# Clock.net
KiCad netlist of a schematic drawn in Altium Designer
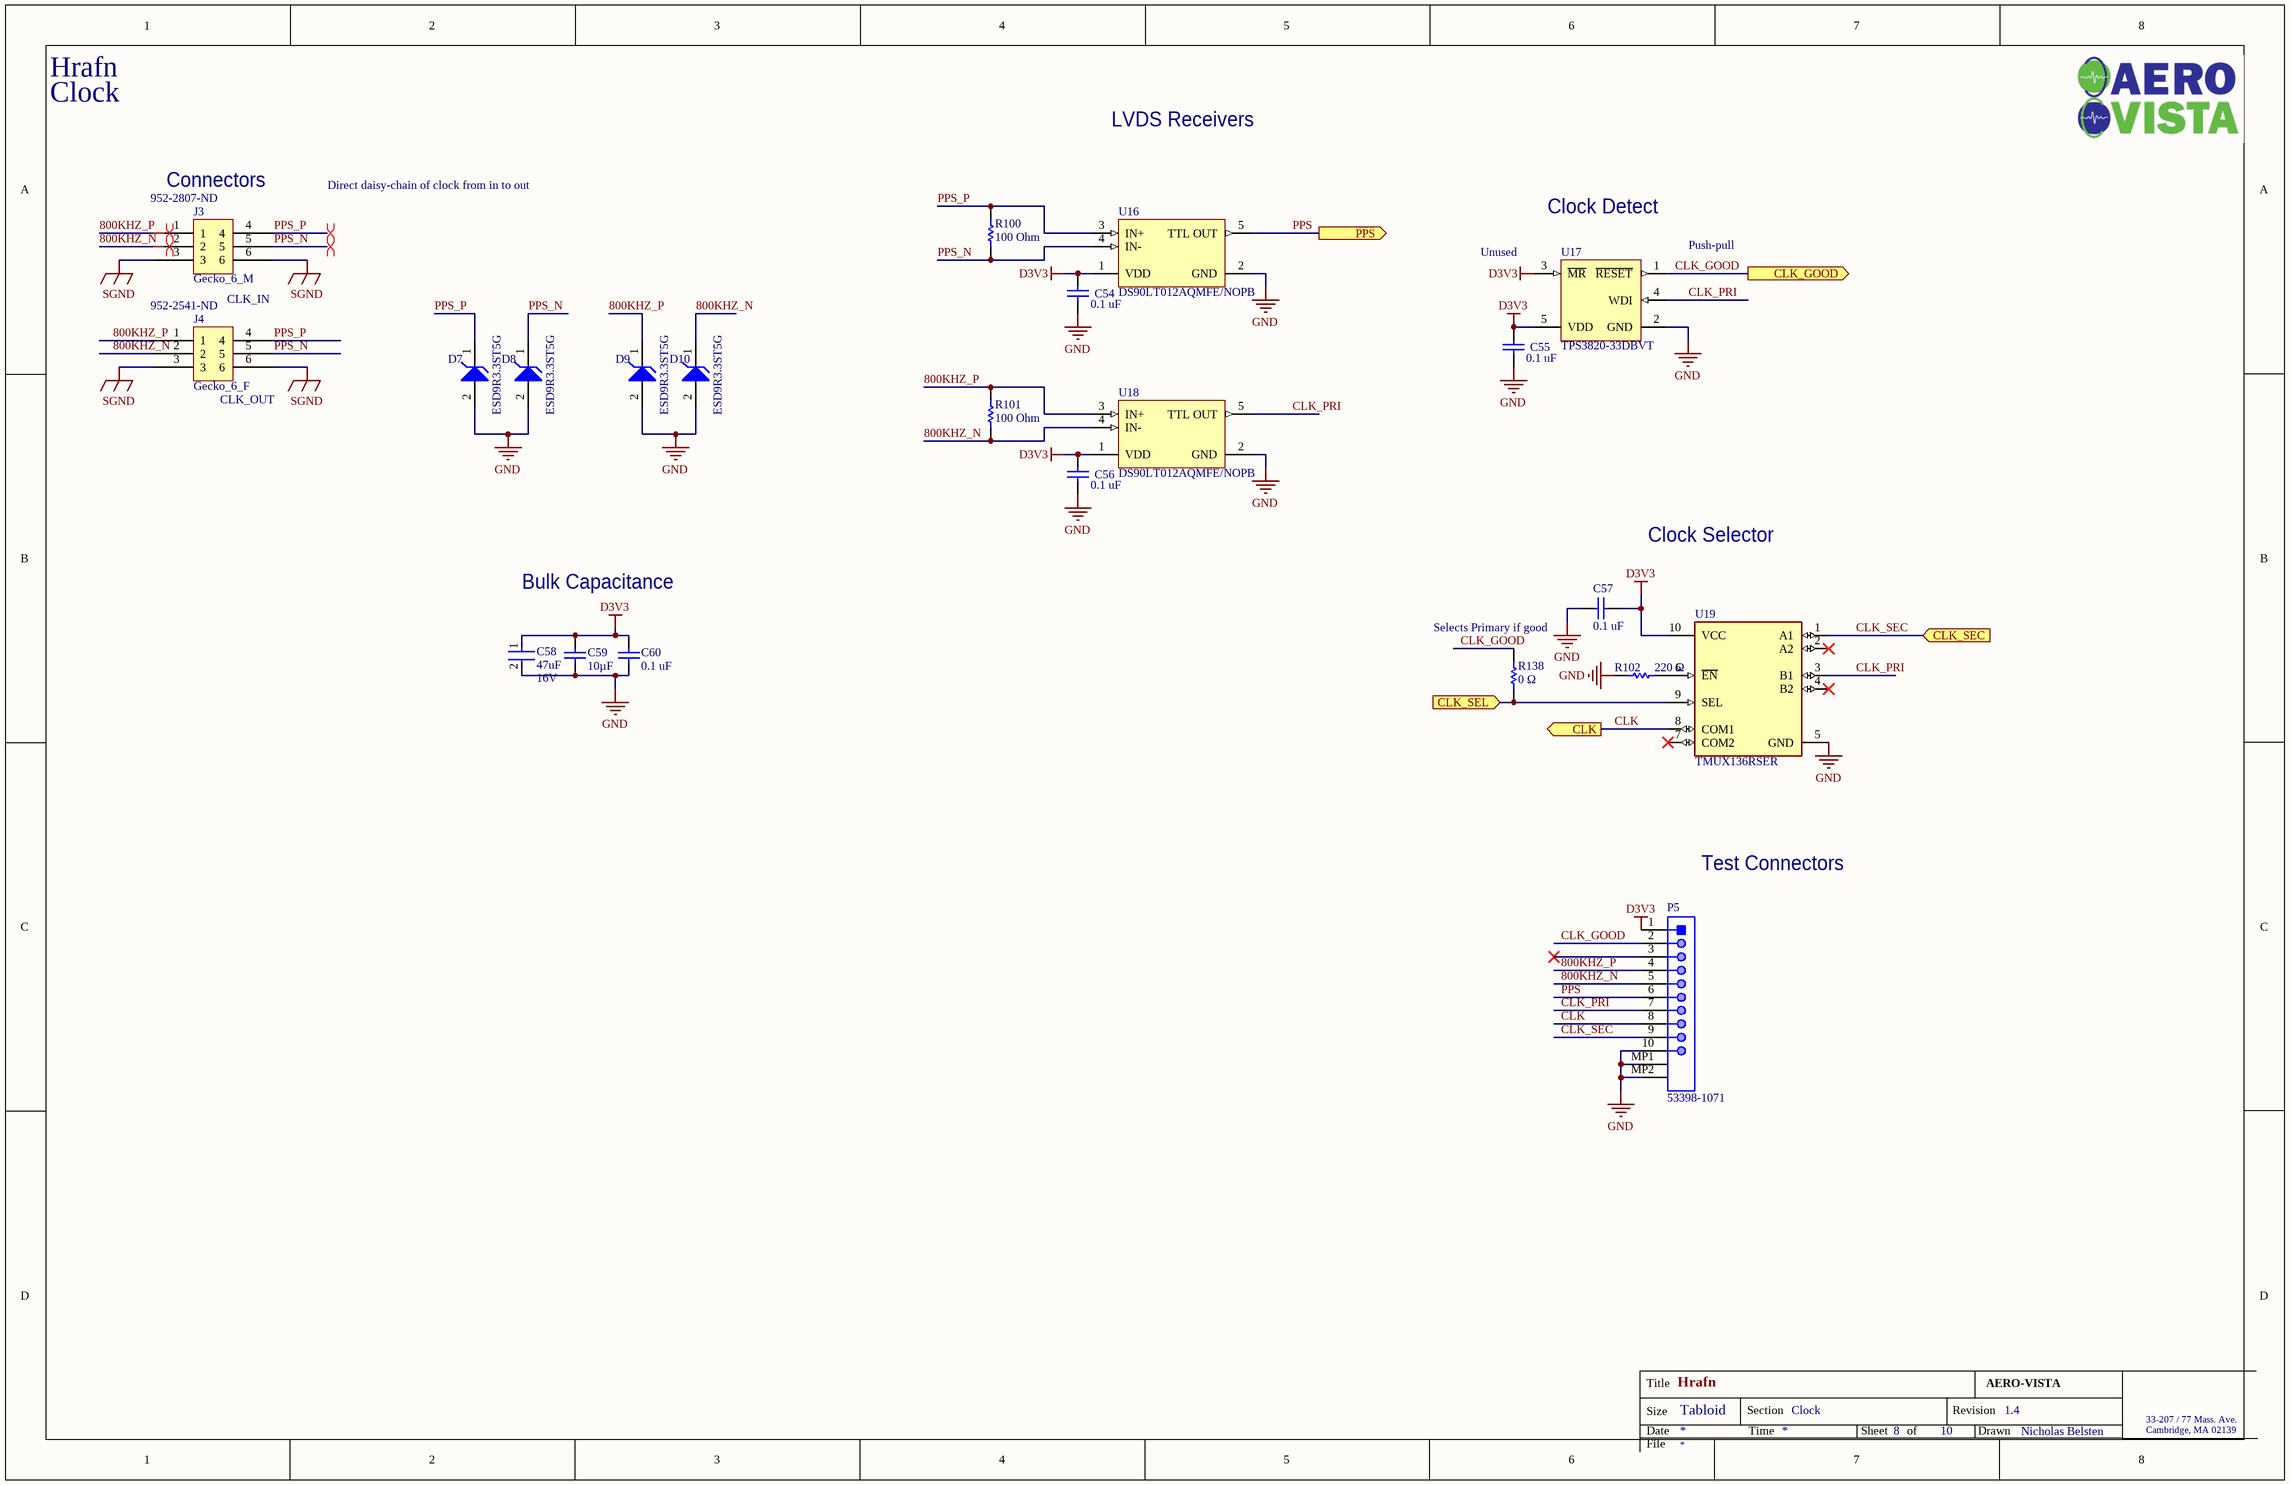
[diagram p0: Clock.SchDoc]

(export (version "E")
  (design (tool "Eeschema 10.0.6"))
  (components
    (comp (ref "C54")
      (value "0.1 uF")
      (footprint "CAPC0402(1005)60_L")
      (description "CAP 100nF 16V ±5% 0402 (1005 Metric) Thickness 0.6mm SMD")
      (fields (field (name "TOLERANCE") "Â±5%"))
      (libsource (lib "Altium Content Vault") (part "CAP"))
    )
    (comp (ref "C55")
      (value "0.1 uF")
      (footprint "CAPC0402(1005)60_L")
      (description "CAP 100nF 16V ±5% 0402 (1005 Metric) Thickness 0.6mm SMD")
      (fields (field (name "TOLERANCE") "Â±5%"))
      (libsource (lib "Altium Content Vault") (part "CAP"))
    )
    (comp (ref "C56")
      (value "0.1 uF")
      (footprint "CAPC0402(1005)60_L")
      (description "CAP 100nF 16V ±5% 0402 (1005 Metric) Thickness 0.6mm SMD")
      (fields (field (name "TOLERANCE") "Â±5%"))
      (libsource (lib "Altium Content Vault") (part "CAP"))
    )
    (comp (ref "C57")
      (value "0.1 uF")
      (footprint "CAPC0402(1005)60_L")
      (description "CAP 100nF 16V ±5% 0402 (1005 Metric) Thickness 0.6mm SMD")
      (fields (field (name "TOLERANCE") "Â±5%"))
      (libsource (lib "Altium Content Vault") (part "CAP"))
    )
    (comp (ref "C58")
      (value "GRT32EC81C476ME13L")
      (footprint "FP-GRT32E-0_3-IPC_C")
      (description "Multi-Layer Ceramic Capacitor 47uF 16V X6S ±20% 1210 Emboss T/R")
      (fields
        (field (name "CAPACITANCE") "47uF")
        (field (name "VOLTAGE RATING") "16V")
        (field (name "TOLERANCE") "20%")
      )
      (libsource (lib "Altium Content Vault") (part "02cd4be3c70576c341d710602a673aa"))
    )
    (comp (ref "C59")
      (value "EMK107BBJ106MA-T")
      (footprint "CAPC1608X100X35LL20T25")
      (description "Chip Capacitor, 10 uF, +/- 20%, 16 V, -55 to 85 degC, 0603 (1608 Metric), RoHS, Tape and Reel")
      (fields
        (field (name "CAPACITANCE") "10µF")
        (field (name "MANUFACTURER") "Taiyo Yuden")
        (field (name "TOLERANCE") "±20%")
      )
      (libsource (lib "Altium Content Vault") (part "CAP-NP-2"))
    )
    (comp (ref "C60")
      (value "0.1 uF")
      (footprint "CAPC0402(1005)60_L")
      (description "CAP 100nF 16V ±5% 0402 (1005 Metric) Thickness 0.6mm SMD")
      (fields (field (name "TOLERANCE") "Â±5%"))
      (libsource (lib "Altium Content Vault") (part "CAP"))
    )
    (comp (ref "D7")
      (value "ESD9R3.3ST5G")
      (footprint "ONSC-SOD-923-2-514AB-01_V")
      (fields (field (name "MANUFACTURER") "On Semiconductor"))
      (libsource (lib "Altium Content Vault") (part "ONSC-K1A2-2_A"))
    )
    (comp (ref "D8")
      (value "ESD9R3.3ST5G")
      (footprint "ONSC-SOD-923-2-514AB-01_V")
      (fields (field (name "MANUFACTURER") "On Semiconductor"))
      (libsource (lib "Altium Content Vault") (part "ONSC-K1A2-2_A"))
    )
    (comp (ref "D9")
      (value "ESD9R3.3ST5G")
      (footprint "ONSC-SOD-923-2-514AB-01_V")
      (fields (field (name "MANUFACTURER") "On Semiconductor"))
      (libsource (lib "Altium Content Vault") (part "ONSC-K1A2-2_A"))
    )
    (comp (ref "D10")
      (value "ESD9R3.3ST5G")
      (footprint "ONSC-SOD-923-2-514AB-01_V")
      (fields (field (name "MANUFACTURER") "On Semiconductor"))
      (libsource (lib "Altium Content Vault") (part "ONSC-K1A2-2_A"))
    )
    (comp (ref "J3")
      (value "Gecko_6_M")
      (footprint "GECK6_M")
      (description "CONN HEADER VERT 6POS 1.25MM")
      (fields (field (name "SUPPLIER PART NUMBER 1") "952-2807-ND"))
      (libsource (lib "Hrafn") (part "Gecko_6_M"))
    )
    (comp (ref "J4")
      (value "Gecko_6_F")
      (footprint "GECK6_F")
      (fields (field (name "SUPPLIER PART NUMBER 1") "952-2541-ND"))
      (libsource (lib "Hrafn") (part "Gecko_6_F"))
    )
    (comp (ref "P5")
      (value "53398-1071")
      (footprint "MOLX-53398-1071_V")
      (description "Male Header, Pitch 1.25 mm, 1 x 10 Position, Height 4.7 mm, -40 to 85 degC, RoHS, Tape and Reel")
      (fields (field (name "MANUFACTURER") "Molex"))
      (libsource (lib "Altium Content Vault") (part "CN-1P-2M-R10"))
    )
    (comp (ref "R100")
      (value "100 Ohm")
      (footprint "RESC1005X40X25LL05T05")
      (description "Chip Resistor, 100 Ohm, +/- 1%, 100 mW, -55 to 155 degC, 0402 (1005 Metric), RoHS, Tape and Reel")
      (fields (field (name "MANUFACTURER") "Basic Passives") (field (name "TOLERANCE") "1%"))
      (libsource (lib "Altium Content Vault") (part "RES-2"))
    )
    (comp (ref "R101")
      (value "100 Ohm")
      (footprint "RESC1005X40X25LL05T05")
      (description "Chip Resistor, 100 Ohm, +/- 1%, 100 mW, -55 to 155 degC, 0402 (1005 Metric), RoHS, Tape and Reel")
      (fields (field (name "MANUFACTURER") "Basic Passives") (field (name "TOLERANCE") "1%"))
      (libsource (lib "Altium Content Vault") (part "RES-2"))
    )
    (comp (ref "R102")
      (value "220 Ω")
      (footprint "RESC1005X40X25LL05T05")
      (fields (field (name "PART NUMBER") "CRCW040220K0FKED") (field (name "MANUFACTURER") "Vishay Dale"))
      (libsource (lib "Altium Content Vault") (part "RES"))
    )
    (comp (ref "R138")
      (value "ERJ2GE0R00X")
      (footprint "RESC1005X40X25LL05T05")
      (description "Chip Resistor, 0 Ohm, 0.1 W, -55 to 155 degC, 0402 (1005 Metric), RoHS, Tape and Reel")
      (fields
        (field (name "MANUFACTURER") "Panasonic")
        (field (name "RESISTANCE") "0 Ω")
        (field (name "TOLERANCE") "5%")
      )
      (libsource (lib "Altium Content Vault") (part "RES-2"))
    )
    (comp (ref "U16")
      (value "DS90LT012AQMFE/NOPB")
      (footprint "MF05A_L")
      (description "Automotive LVDS Differential Line Receiver, 5-pin SOT-23, Pb-Free")
      (fields (field (name "MANUFACTURER") "National Semiconductor"))
      (libsource (lib "Altium Content Vault") (part "IN-LNRX-DS90LT012ATMF"))
    )
    (comp (ref "U17")
      (value "TPS3820-33DBVT")
      (footprint "DBV0005A_N")
      (fields (field (name "MANUFACTURER") "Texas Instruments"))
      (libsource (lib "Altium Content Vault") (part "TI-TPS3820-33DBV5"))
    )
    (comp (ref "U18")
      (value "DS90LT012AQMFE/NOPB")
      (footprint "MF05A_L")
      (description "Automotive LVDS Differential Line Receiver, 5-pin SOT-23, Pb-Free")
      (fields (field (name "MANUFACTURER") "National Semiconductor"))
      (libsource (lib "Altium Content Vault") (part "IN-LNRX-DS90LT012ATMF"))
    )
    (comp (ref "U19")
      (value "TMUX136RSER")
      (footprint "FP-RSE0010A-MFG")
      (description "IC SWITCH SPDT DUAL 10UQFN")
      (fields
        (field (name "OCTOPART") "https://octopart.com/tmux136rser-texas+instruments-86728646")
        (field (name "MANUFACTURER") "Texas Instruments")
      )
      (libsource (lib "Altium Content Vault") (part "ccc234045474e6887f4445d0784f813"))
    )
  )
  (nets
    (net (code "1") (name "/800KHZ_N") (class "Default")
      (node (ref "D10") (pin "1") (pinfunction "K_1") (pintype "passive"))
      (node (ref "J3") (pin "2") (pinfunction "2_2") (pintype "passive"))
      (node (ref "J4") (pin "2") (pinfunction "2_2") (pintype "passive"))
      (node (ref "P5") (pin "5") (pinfunction "5_5") (pintype "passive"))
      (node (ref "R101") (pin "1") (pinfunction "1_1") (pintype "passive"))
      (node (ref "U18") (pin "4") (pinfunction "IN-_4") (pintype "input"))
    )
    (net (code "2") (name "/800KHZ_P") (class "Default")
      (node (ref "D9") (pin "1") (pinfunction "K_1") (pintype "passive"))
      (node (ref "J3") (pin "1") (pinfunction "1_1") (pintype "passive"))
      (node (ref "J4") (pin "1") (pinfunction "1_1") (pintype "passive"))
      (node (ref "P5") (pin "4") (pinfunction "4_4") (pintype "passive"))
      (node (ref "R101") (pin "2") (pinfunction "2_2") (pintype "passive"))
      (node (ref "U18") (pin "3") (pinfunction "IN+_3") (pintype "input"))
    )
    (net (code "3") (name "/CLK") (class "Default")
      (node (ref "P5") (pin "8") (pinfunction "8_8") (pintype "passive"))
      (node (ref "U19") (pin "8") (pinfunction "COM1_8") (pintype "bidirectional"))
    )
    (net (code "4") (name "/CLK_GOOD") (class "Default")
      (node (ref "P5") (pin "2") (pinfunction "2_2") (pintype "passive"))
      (node (ref "R138") (pin "2") (pinfunction "2_2") (pintype "passive"))
      (node (ref "U17") (pin "1") (pinfunction "~{RESET}_1") (pintype "output"))
    )
    (net (code "5") (name "/CLK_PRI") (class "Default")
      (node (ref "P5") (pin "7") (pinfunction "7_7") (pintype "passive"))
      (node (ref "U17") (pin "4") (pinfunction "WDI_4") (pintype "input"))
      (node (ref "U18") (pin "5") (pinfunction "TTL_OUT_5") (pintype "output"))
      (node (ref "U19") (pin "3") (pinfunction "B1_3") (pintype "bidirectional"))
    )
    (net (code "6") (name "/CLK_SEC") (class "Default")
      (node (ref "P5") (pin "9") (pinfunction "9_9") (pintype "passive"))
      (node (ref "U19") (pin "1") (pinfunction "A1_1") (pintype "bidirectional"))
    )
    (net (code "7") (name "/CLK_SEL") (class "Default")
      (node (ref "R138") (pin "1") (pinfunction "1_1") (pintype "passive"))
      (node (ref "U19") (pin "9") (pinfunction "SEL_9") (pintype "input"))
    )
    (net (code "8") (name "/PPS") (class "Default")
      (node (ref "P5") (pin "6") (pinfunction "6_6") (pintype "passive"))
      (node (ref "U16") (pin "5") (pinfunction "TTL_OUT_5") (pintype "output"))
    )
    (net (code "9") (name "/PPS_N") (class "Default")
      (node (ref "D8") (pin "1") (pinfunction "K_1") (pintype "passive"))
      (node (ref "J3") (pin "5") (pinfunction "5_5") (pintype "passive"))
      (node (ref "J4") (pin "5") (pinfunction "5_5") (pintype "passive"))
      (node (ref "R100") (pin "1") (pinfunction "1_1") (pintype "passive"))
      (node (ref "U16") (pin "4") (pinfunction "IN-_4") (pintype "input"))
    )
    (net (code "10") (name "/PPS_P") (class "Default")
      (node (ref "D7") (pin "1") (pinfunction "K_1") (pintype "passive"))
      (node (ref "J3") (pin "4") (pinfunction "4_4") (pintype "passive"))
      (node (ref "J4") (pin "4") (pinfunction "4_4") (pintype "passive"))
      (node (ref "R100") (pin "2") (pinfunction "2_2") (pintype "passive"))
      (node (ref "U16") (pin "3") (pinfunction "IN+_3") (pintype "input"))
    )
    (net (code "11") (name "D3V3") (class "Default")
      (node (ref "C54") (pin "2") (pinfunction "2_2") (pintype "passive"))
      (node (ref "C55") (pin "2") (pinfunction "2_2") (pintype "passive"))
      (node (ref "C56") (pin "2") (pinfunction "2_2") (pintype "passive"))
      (node (ref "C57") (pin "1") (pinfunction "1_1") (pintype "passive"))
      (node (ref "C58") (pin "1") (pinfunction "1_1") (pintype "passive"))
      (node (ref "C59") (pin "2") (pinfunction "2_2") (pintype "passive"))
      (node (ref "C60") (pin "2") (pinfunction "2_2") (pintype "passive"))
      (node (ref "P5") (pin "1") (pinfunction "1_1") (pintype "passive"))
      (node (ref "U16") (pin "1") (pinfunction "VDD_1") (pintype "power_in"))
      (node (ref "U17") (pin "3") (pinfunction "~{MR}_3") (pintype "input"))
      (node (ref "U17") (pin "5") (pinfunction "VDD_5") (pintype "power_in"))
      (node (ref "U18") (pin "1") (pinfunction "VDD_1") (pintype "power_in"))
      (node (ref "U19") (pin "10") (pinfunction "VCC_10") (pintype "power_in"))
    )
    (net (code "12") (name "GND") (class "Default")
      (node (ref "C54") (pin "1") (pinfunction "1_1") (pintype "passive"))
      (node (ref "C55") (pin "1") (pinfunction "1_1") (pintype "passive"))
      (node (ref "C56") (pin "1") (pinfunction "1_1") (pintype "passive"))
      (node (ref "C57") (pin "2") (pinfunction "2_2") (pintype "passive"))
      (node (ref "C58") (pin "2") (pinfunction "2_2") (pintype "passive"))
      (node (ref "C59") (pin "1") (pinfunction "1_1") (pintype "passive"))
      (node (ref "C60") (pin "1") (pinfunction "1_1") (pintype "passive"))
      (node (ref "D10") (pin "2") (pinfunction "A_2") (pintype "passive"))
      (node (ref "D7") (pin "2") (pinfunction "A_2") (pintype "passive"))
      (node (ref "D8") (pin "2") (pinfunction "A_2") (pintype "passive"))
      (node (ref "D9") (pin "2") (pinfunction "A_2") (pintype "passive"))
      (node (ref "P5") (pin "10") (pinfunction "10_10") (pintype "passive"))
      (node (ref "P5") (pin "MP1") (pinfunction "MP1_MP1") (pintype "passive"))
      (node (ref "P5") (pin "MP2") (pinfunction "MP2_MP2") (pintype "passive"))
      (node (ref "R102") (pin "1") (pinfunction "1_1") (pintype "passive"))
      (node (ref "U16") (pin "2") (pinfunction "GND_2") (pintype "power_in"))
      (node (ref "U17") (pin "2") (pinfunction "GND_2") (pintype "power_in"))
      (node (ref "U18") (pin "2") (pinfunction "GND_2") (pintype "power_in"))
      (node (ref "U19") (pin "5") (pinfunction "GND_5") (pintype "power_in"))
    )
    (net (code "13") (name "Net-(U19-~{EN})") (class "Default")
      (node (ref "R102") (pin "2") (pinfunction "2_2") (pintype "passive"))
      (node (ref "U19") (pin "6") (pinfunction "~{EN}_6") (pintype "input"))
    )
    (net (code "14") (name "SGND") (class "Default")
      (node (ref "J3") (pin "3") (pinfunction "3_3") (pintype "passive"))
      (node (ref "J3") (pin "6") (pinfunction "6_6") (pintype "passive"))
      (node (ref "J4") (pin "3") (pinfunction "3_3") (pintype "passive"))
      (node (ref "J4") (pin "6") (pinfunction "6_6") (pintype "passive"))
    )
    (net (code "15") (name "unconnected-(P5-Pad3)") (class "Default")
      (node (ref "P5") (pin "3") (pinfunction "3_3") (pintype "passive+no_connect"))
    )
    (net (code "16") (name "unconnected-(U19-A2-Pad2)") (class "Default")
      (node (ref "U19") (pin "2") (pinfunction "A2_2") (pintype "bidirectional+no_connect"))
    )
    (net (code "17") (name "unconnected-(U19-B2-Pad4)") (class "Default")
      (node (ref "U19") (pin "4") (pinfunction "B2_4") (pintype "bidirectional+no_connect"))
    )
    (net (code "18") (name "unconnected-(U19-COM2-Pad7)") (class "Default")
      (node (ref "U19") (pin "7") (pinfunction "COM2_7") (pintype "bidirectional+no_connect"))
    )
  )
)
